# timer.net
KiCad netlist of a schematic drawn in Altium Designer
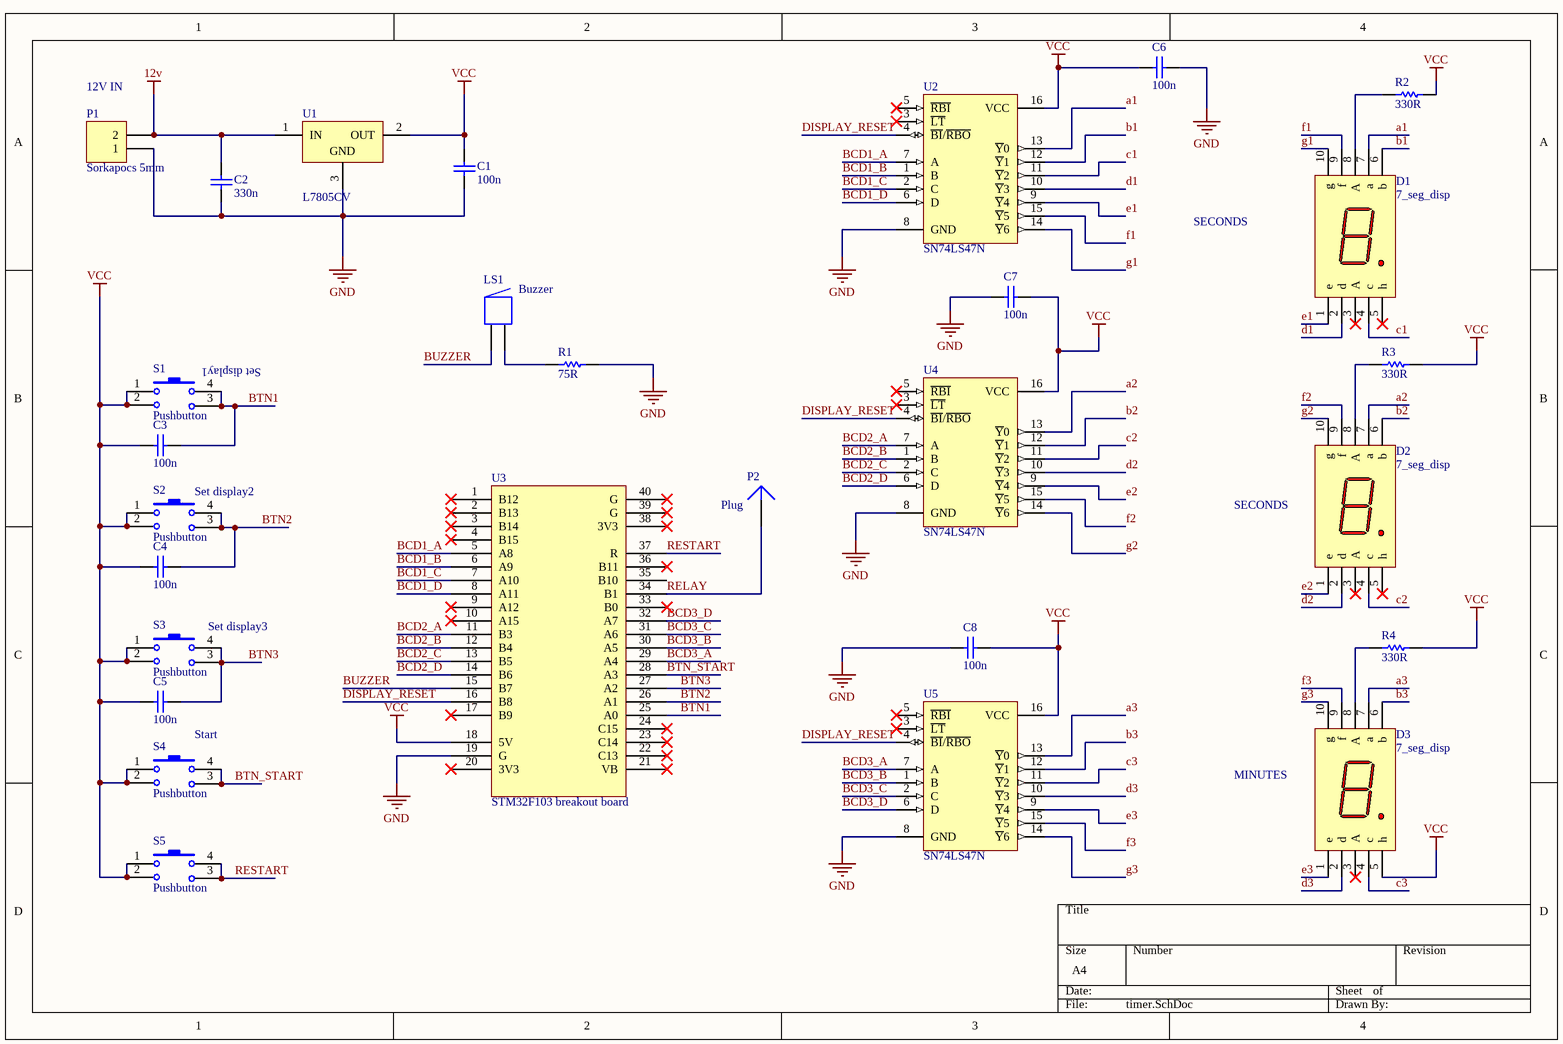
[diagram p0: timer.SchDoc]

(export (version "E")
  (design (tool "Eeschema 10.0.6"))
  (components
    (comp (ref "C1")
      (value "100n")
      (footprint "cap 100mil")
      (description "Capacitor")
      (fields (field (name "PUBLISHER") "Altium Limited"))
      (libsource (lib "Miscellaneous Devices") (part "Cap"))
    )
    (comp (ref "C2")
      (value "330n")
      (footprint "cap 5mm")
      (description "Capacitor")
      (fields (field (name "PUBLISHER") "Altium Limited"))
      (libsource (lib "Miscellaneous Devices") (part "Cap"))
    )
    (comp (ref "C3")
      (value "100n")
      (footprint "cap 100mil")
      (description "Capacitor")
      (fields (field (name "PUBLISHER") "Altium Limited"))
      (libsource (lib "Miscellaneous Devices") (part "Cap"))
    )
    (comp (ref "C4")
      (value "100n")
      (footprint "cap 100mil")
      (description "Capacitor")
      (fields (field (name "PUBLISHER") "Altium Limited"))
      (libsource (lib "Miscellaneous Devices") (part "Cap"))
    )
    (comp (ref "C5")
      (value "100n")
      (footprint "cap 100mil")
      (description "Capacitor")
      (fields (field (name "PUBLISHER") "Altium Limited"))
      (libsource (lib "Miscellaneous Devices") (part "Cap"))
    )
    (comp (ref "C6")
      (value "100n")
      (footprint "cap 100mil")
      (description "Capacitor")
      (fields (field (name "PUBLISHER") "Altium Limited"))
      (libsource (lib "Miscellaneous Devices") (part "Cap"))
    )
    (comp (ref "C7")
      (value "100n")
      (footprint "cap 100mil")
      (description "Capacitor")
      (fields (field (name "PUBLISHER") "Altium Limited"))
      (libsource (lib "Miscellaneous Devices") (part "Cap"))
    )
    (comp (ref "C8")
      (value "100n")
      (footprint "cap 100mil")
      (description "Capacitor")
      (fields (field (name "PUBLISHER") "Altium Limited"))
      (libsource (lib "Miscellaneous Devices") (part "Cap"))
    )
    (comp (ref "D1")
      (value "7_seg_disp")
      (footprint "Seven segment display")
      (libsource (lib "mySchematics") (part "7_seg_disp"))
    )
    (comp (ref "D2")
      (value "7_seg_disp")
      (footprint "Seven segment display")
      (libsource (lib "mySchematics") (part "7_seg_disp"))
    )
    (comp (ref "D3")
      (value "7_seg_disp")
      (footprint "Seven segment display")
      (libsource (lib "mySchematics") (part "7_seg_disp"))
    )
    (comp (ref "LS1")
      (value "Buzzer")
      (footprint "Buzzer")
      (description "Magnetic Transducer Buzzer")
      (fields (field (name "PUBLISHER") "Altium Limited"))
      (libsource (lib "Miscellaneous Devices") (part "Buzzer"))
    )
    (comp (ref "P1")
      (value "Sorkapocs 5mm")
      (footprint "SORKAPOCS-2")
      (description "Header, 2-Pin")
      (fields (field (name "PUBLISHER") "Altium Limited"))
      (libsource (lib "Miscellaneous Connectors") (part "Header 2"))
    )
    (comp (ref "P2")
      (value "Plug")
      (footprint "pad")
      (fields (field (name "PUBLISHER") "Altium Limited"))
      (libsource (lib "Miscellaneous Connectors") (part "Plug"))
    )
    (comp (ref "R1")
      (value "75R")
      (footprint "AXIAL-0.4")
      (description "Resistor")
      (fields (field (name "PUBLISHER") "Altium Limited"))
      (libsource (lib "Miscellaneous Devices") (part "Res1"))
    )
    (comp (ref "R2")
      (value "330R")
      (footprint "AXIAL-0.4")
      (description "Resistor")
      (fields (field (name "PUBLISHER") "Altium Limited"))
      (libsource (lib "Miscellaneous Devices") (part "Res1"))
    )
    (comp (ref "R3")
      (value "330R")
      (footprint "AXIAL-0.4")
      (description "Resistor")
      (fields (field (name "PUBLISHER") "Altium Limited"))
      (libsource (lib "Miscellaneous Devices") (part "Res1"))
    )
    (comp (ref "R4")
      (value "330R")
      (footprint "AXIAL-0.4")
      (description "Resistor")
      (fields (field (name "PUBLISHER") "Altium Limited"))
      (libsource (lib "Miscellaneous Devices") (part "Res1"))
    )
    (comp (ref "S1")
      (value "Pushbutton")
      (footprint "Pushbutton")
      (description "FSM2JSMLS -  Tactile Switch, Illuminated, 24 V, 50 mA, 100 gf, SMD, FSMJSM Series")
      (libsource (lib "mySchematics") (part "Tactile switch"))
    )
    (comp (ref "S2")
      (value "Pushbutton")
      (footprint "Pushbutton")
      (description "FSM2JSMLS -  Tactile Switch, Illuminated, 24 V, 50 mA, 100 gf, SMD, FSMJSM Series")
      (libsource (lib "mySchematics") (part "Tactile switch"))
    )
    (comp (ref "S3")
      (value "Pushbutton")
      (footprint "Pushbutton")
      (description "FSM2JSMLS -  Tactile Switch, Illuminated, 24 V, 50 mA, 100 gf, SMD, FSMJSM Series")
      (libsource (lib "mySchematics") (part "Tactile switch"))
    )
    (comp (ref "S4")
      (value "Pushbutton")
      (footprint "Pushbutton")
      (description "FSM2JSMLS -  Tactile Switch, Illuminated, 24 V, 50 mA, 100 gf, SMD, FSMJSM Series")
      (libsource (lib "mySchematics") (part "Tactile switch"))
    )
    (comp (ref "S5")
      (value "Pushbutton")
      (footprint "Pushbutton")
      (description "FSM2JSMLS -  Tactile Switch, Illuminated, 24 V, 50 mA, 100 gf, SMD, FSMJSM Series")
      (libsource (lib "mySchematics") (part "Tactile switch"))
    )
    (comp (ref "U1")
      (value "L7805CV")
      (footprint "TO220ABN")
      (description "Positive Voltage Regulator")
      (fields (field (name "PUBLISHER") "Altium Limited"))
      (libsource (lib "ST Power Mgt Voltage Regulator") (part "L7805CV"))
    )
    (comp (ref "U2")
      (value "SN74LS47N")
      (footprint "648-08")
      (description "BCD to 7-Segment Decoder/Driver")
      (fields (field (name "PUBLISHER") "Altium Limited"))
      (libsource (lib "ON Semi Logic Decoder Demux") (part "SN74LS47N"))
    )
    (comp (ref "U3")
      (value "STM32F103 breakout board")
      (footprint "STM32 BLUE PILL")
      (libsource (lib "mySchematics") (part "STM32F103 breakout board"))
    )
    (comp (ref "U4")
      (value "SN74LS47N")
      (footprint "648-08")
      (description "BCD to 7-Segment Decoder/Driver")
      (fields (field (name "PUBLISHER") "Altium Limited"))
      (libsource (lib "ON Semi Logic Decoder Demux") (part "SN74LS47N"))
    )
    (comp (ref "U5")
      (value "SN74LS47N")
      (footprint "648-08")
      (description "BCD to 7-Segment Decoder/Driver")
      (fields (field (name "PUBLISHER") "Altium Limited"))
      (libsource (lib "ON Semi Logic Decoder Demux") (part "SN74LS47N"))
    )
  )
  (nets
    (net (code "1") (name "/BCD1_A") (class "Default")
      (node (ref "U2") (pin "7") (pinfunction "A_7") (pintype "input"))
      (node (ref "U3") (pin "5") (pinfunction "A8_5") (pintype "passive"))
    )
    (net (code "2") (name "/BCD1_B") (class "Default")
      (node (ref "U2") (pin "1") (pinfunction "B_1") (pintype "input"))
      (node (ref "U3") (pin "6") (pinfunction "A9_6") (pintype "passive"))
    )
    (net (code "3") (name "/BCD1_C") (class "Default")
      (node (ref "U2") (pin "2") (pinfunction "C_2") (pintype "input"))
      (node (ref "U3") (pin "7") (pinfunction "A10_7") (pintype "passive"))
    )
    (net (code "4") (name "/BCD1_D") (class "Default")
      (node (ref "U2") (pin "6") (pinfunction "D_6") (pintype "input"))
      (node (ref "U3") (pin "8") (pinfunction "A11_8") (pintype "passive"))
    )
    (net (code "5") (name "/BCD2_A") (class "Default")
      (node (ref "U3") (pin "11") (pinfunction "B3_11") (pintype "passive"))
      (node (ref "U4") (pin "7") (pinfunction "A_7") (pintype "input"))
    )
    (net (code "6") (name "/BCD2_B") (class "Default")
      (node (ref "U3") (pin "12") (pinfunction "B4_12") (pintype "passive"))
      (node (ref "U4") (pin "1") (pinfunction "B_1") (pintype "input"))
    )
    (net (code "7") (name "/BCD2_C") (class "Default")
      (node (ref "U3") (pin "13") (pinfunction "B5_13") (pintype "passive"))
      (node (ref "U4") (pin "2") (pinfunction "C_2") (pintype "input"))
    )
    (net (code "8") (name "/BCD2_D") (class "Default")
      (node (ref "U3") (pin "14") (pinfunction "B6_14") (pintype "passive"))
      (node (ref "U4") (pin "6") (pinfunction "D_6") (pintype "input"))
    )
    (net (code "9") (name "/BCD3_A") (class "Default")
      (node (ref "U3") (pin "29") (pinfunction "A4_29") (pintype "passive"))
      (node (ref "U5") (pin "7") (pinfunction "A_7") (pintype "input"))
    )
    (net (code "10") (name "/BCD3_B") (class "Default")
      (node (ref "U3") (pin "30") (pinfunction "A5_30") (pintype "passive"))
      (node (ref "U5") (pin "1") (pinfunction "B_1") (pintype "input"))
    )
    (net (code "11") (name "/BCD3_C") (class "Default")
      (node (ref "U3") (pin "31") (pinfunction "A6_31") (pintype "passive"))
      (node (ref "U5") (pin "2") (pinfunction "C_2") (pintype "input"))
    )
    (net (code "12") (name "/BCD3_D") (class "Default")
      (node (ref "U3") (pin "32") (pinfunction "A7_32") (pintype "passive"))
      (node (ref "U5") (pin "6") (pinfunction "D_6") (pintype "input"))
    )
    (net (code "13") (name "/BTN1") (class "Default")
      (node (ref "C3") (pin "1") (pinfunction "1_1") (pintype "passive"))
      (node (ref "S1") (pin "3") (pinfunction "3_3") (pintype "passive"))
      (node (ref "S1") (pin "4") (pinfunction "4_4") (pintype "passive"))
      (node (ref "U3") (pin "25") (pinfunction "A0_25") (pintype "passive"))
    )
    (net (code "14") (name "/BTN2") (class "Default")
      (node (ref "C4") (pin "1") (pinfunction "1_1") (pintype "passive"))
      (node (ref "S2") (pin "3") (pinfunction "3_3") (pintype "passive"))
      (node (ref "S2") (pin "4") (pinfunction "4_4") (pintype "passive"))
      (node (ref "U3") (pin "26") (pinfunction "A1_26") (pintype "passive"))
    )
    (net (code "15") (name "/BTN3") (class "Default")
      (node (ref "C5") (pin "1") (pinfunction "1_1") (pintype "passive"))
      (node (ref "S3") (pin "3") (pinfunction "3_3") (pintype "passive"))
      (node (ref "S3") (pin "4") (pinfunction "4_4") (pintype "passive"))
      (node (ref "U3") (pin "27") (pinfunction "A2_27") (pintype "passive"))
    )
    (net (code "16") (name "/BTN_START") (class "Default")
      (node (ref "S4") (pin "3") (pinfunction "3_3") (pintype "passive"))
      (node (ref "S4") (pin "4") (pinfunction "4_4") (pintype "passive"))
      (node (ref "U3") (pin "28") (pinfunction "A3_28") (pintype "passive"))
    )
    (net (code "17") (name "/BUZZER") (class "Default")
      (node (ref "LS1") (pin "1") (pinfunction "1_1") (pintype "passive"))
      (node (ref "U3") (pin "15") (pinfunction "B7_15") (pintype "passive"))
    )
    (net (code "18") (name "/DISPLAY_RESET") (class "Default")
      (node (ref "U2") (pin "4") (pinfunction "~{BI}/~{RBO}_4") (pintype "bidirectional"))
      (node (ref "U3") (pin "16") (pinfunction "B8_16") (pintype "passive"))
      (node (ref "U4") (pin "4") (pinfunction "~{BI}/~{RBO}_4") (pintype "bidirectional"))
      (node (ref "U5") (pin "4") (pinfunction "~{BI}/~{RBO}_4") (pintype "bidirectional"))
    )
    (net (code "19") (name "/RELAY") (class "Default")
      (node (ref "P2") (pin "1") (pinfunction "1_1") (pintype "passive"))
      (node (ref "U3") (pin "34") (pinfunction "B1_34") (pintype "passive"))
    )
    (net (code "20") (name "/RESTART") (class "Default")
      (node (ref "S5") (pin "3") (pinfunction "3_3") (pintype "passive"))
      (node (ref "S5") (pin "4") (pinfunction "4_4") (pintype "passive"))
      (node (ref "U3") (pin "37") (pinfunction "R_37") (pintype "passive"))
    )
    (net (code "21") (name "/a1") (class "Default")
      (node (ref "D1") (pin "7") (pinfunction "a_7") (pintype "passive"))
      (node (ref "U2") (pin "13") (pinfunction "~{Y}0_13") (pintype "output"))
    )
    (net (code "22") (name "/a2") (class "Default")
      (node (ref "D2") (pin "7") (pinfunction "a_7") (pintype "passive"))
      (node (ref "U4") (pin "13") (pinfunction "~{Y}0_13") (pintype "output"))
    )
    (net (code "23") (name "/a3") (class "Default")
      (node (ref "D3") (pin "7") (pinfunction "a_7") (pintype "passive"))
      (node (ref "U5") (pin "13") (pinfunction "~{Y}0_13") (pintype "output"))
    )
    (net (code "24") (name "/b1") (class "Default")
      (node (ref "D1") (pin "6") (pinfunction "b_6") (pintype "passive"))
      (node (ref "U2") (pin "12") (pinfunction "~{Y}1_12") (pintype "output"))
    )
    (net (code "25") (name "/b2") (class "Default")
      (node (ref "D2") (pin "6") (pinfunction "b_6") (pintype "passive"))
      (node (ref "U4") (pin "12") (pinfunction "~{Y}1_12") (pintype "output"))
    )
    (net (code "26") (name "/b3") (class "Default")
      (node (ref "D3") (pin "6") (pinfunction "b_6") (pintype "passive"))
      (node (ref "U5") (pin "12") (pinfunction "~{Y}1_12") (pintype "output"))
    )
    (net (code "27") (name "/c1") (class "Default")
      (node (ref "D1") (pin "4") (pinfunction "c_4") (pintype "passive"))
      (node (ref "U2") (pin "11") (pinfunction "~{Y}2_11") (pintype "output"))
    )
    (net (code "28") (name "/c2") (class "Default")
      (node (ref "D2") (pin "4") (pinfunction "c_4") (pintype "passive"))
      (node (ref "U4") (pin "11") (pinfunction "~{Y}2_11") (pintype "output"))
    )
    (net (code "29") (name "/c3") (class "Default")
      (node (ref "D3") (pin "4") (pinfunction "c_4") (pintype "passive"))
      (node (ref "U5") (pin "11") (pinfunction "~{Y}2_11") (pintype "output"))
    )
    (net (code "30") (name "/d1") (class "Default")
      (node (ref "D1") (pin "2") (pinfunction "d_2") (pintype "passive"))
      (node (ref "U2") (pin "10") (pinfunction "~{Y}3_10") (pintype "output"))
    )
    (net (code "31") (name "/d2") (class "Default")
      (node (ref "D2") (pin "2") (pinfunction "d_2") (pintype "passive"))
      (node (ref "U4") (pin "10") (pinfunction "~{Y}3_10") (pintype "output"))
    )
    (net (code "32") (name "/d3") (class "Default")
      (node (ref "D3") (pin "2") (pinfunction "d_2") (pintype "passive"))
      (node (ref "U5") (pin "10") (pinfunction "~{Y}3_10") (pintype "output"))
    )
    (net (code "33") (name "/e1") (class "Default")
      (node (ref "D1") (pin "1") (pinfunction "e_1") (pintype "passive"))
      (node (ref "U2") (pin "9") (pinfunction "~{Y}4_9") (pintype "output"))
    )
    (net (code "34") (name "/e2") (class "Default")
      (node (ref "D2") (pin "1") (pinfunction "e_1") (pintype "passive"))
      (node (ref "U4") (pin "9") (pinfunction "~{Y}4_9") (pintype "output"))
    )
    (net (code "35") (name "/e3") (class "Default")
      (node (ref "D3") (pin "1") (pinfunction "e_1") (pintype "passive"))
      (node (ref "U5") (pin "9") (pinfunction "~{Y}4_9") (pintype "output"))
    )
    (net (code "36") (name "/f1") (class "Default")
      (node (ref "D1") (pin "9") (pinfunction "f_9") (pintype "passive"))
      (node (ref "U2") (pin "15") (pinfunction "~{Y}5_15") (pintype "output"))
    )
    (net (code "37") (name "/f2") (class "Default")
      (node (ref "D2") (pin "9") (pinfunction "f_9") (pintype "passive"))
      (node (ref "U4") (pin "15") (pinfunction "~{Y}5_15") (pintype "output"))
    )
    (net (code "38") (name "/f3") (class "Default")
      (node (ref "D3") (pin "9") (pinfunction "f_9") (pintype "passive"))
      (node (ref "U5") (pin "15") (pinfunction "~{Y}5_15") (pintype "output"))
    )
    (net (code "39") (name "/g1") (class "Default")
      (node (ref "D1") (pin "10") (pinfunction "g_10") (pintype "passive"))
      (node (ref "U2") (pin "14") (pinfunction "~{Y}6_14") (pintype "output"))
    )
    (net (code "40") (name "/g2") (class "Default")
      (node (ref "D2") (pin "10") (pinfunction "g_10") (pintype "passive"))
      (node (ref "U4") (pin "14") (pinfunction "~{Y}6_14") (pintype "output"))
    )
    (net (code "41") (name "/g3") (class "Default")
      (node (ref "D3") (pin "10") (pinfunction "g_10") (pintype "passive"))
      (node (ref "U5") (pin "14") (pinfunction "~{Y}6_14") (pintype "output"))
    )
    (net (code "42") (name "12v") (class "Default")
      (node (ref "C2") (pin "2") (pinfunction "2_2") (pintype "passive"))
      (node (ref "P1") (pin "2") (pinfunction "2_2") (pintype "passive"))
      (node (ref "U1") (pin "1") (pinfunction "IN_1") (pintype "power_in"))
    )
    (net (code "43") (name "GND") (class "Default")
      (node (ref "C1") (pin "1") (pinfunction "1_1") (pintype "passive"))
      (node (ref "C2") (pin "1") (pinfunction "1_1") (pintype "passive"))
      (node (ref "C6") (pin "1") (pinfunction "1_1") (pintype "passive"))
      (node (ref "C7") (pin "2") (pinfunction "2_2") (pintype "passive"))
      (node (ref "C8") (pin "2") (pinfunction "2_2") (pintype "passive"))
      (node (ref "P1") (pin "1") (pinfunction "1_1") (pintype "passive"))
      (node (ref "R1") (pin "2") (pinfunction "2_2") (pintype "passive"))
      (node (ref "U1") (pin "3") (pinfunction "GND_3") (pintype "power_in"))
      (node (ref "U2") (pin "8") (pinfunction "GND_8") (pintype "power_in"))
      (node (ref "U3") (pin "19") (pinfunction "G_19") (pintype "passive"))
      (node (ref "U4") (pin "8") (pinfunction "GND_8") (pintype "power_in"))
      (node (ref "U5") (pin "8") (pinfunction "GND_8") (pintype "power_in"))
    )
    (net (code "44") (name "Net-(D1-A-Pad8)") (class "Default")
      (node (ref "D1") (pin "8") (pinfunction "A_8") (pintype "passive"))
      (node (ref "R2") (pin "1") (pinfunction "1_1") (pintype "passive"))
    )
    (net (code "45") (name "Net-(D2-A-Pad8)") (class "Default")
      (node (ref "D2") (pin "8") (pinfunction "A_8") (pintype "passive"))
      (node (ref "R3") (pin "1") (pinfunction "1_1") (pintype "passive"))
    )
    (net (code "46") (name "Net-(D3-A-Pad8)") (class "Default")
      (node (ref "D3") (pin "8") (pinfunction "A_8") (pintype "passive"))
      (node (ref "R4") (pin "1") (pinfunction "1_1") (pintype "passive"))
    )
    (net (code "47") (name "Net-(LS1-Pad2)") (class "Default")
      (node (ref "LS1") (pin "2") (pinfunction "2_2") (pintype "passive"))
      (node (ref "R1") (pin "1") (pinfunction "1_1") (pintype "passive"))
    )
    (net (code "48") (name "VCC") (class "Default")
      (node (ref "C1") (pin "2") (pinfunction "2_2") (pintype "passive"))
      (node (ref "C3") (pin "2") (pinfunction "2_2") (pintype "passive"))
      (node (ref "C4") (pin "2") (pinfunction "2_2") (pintype "passive"))
      (node (ref "C5") (pin "2") (pinfunction "2_2") (pintype "passive"))
      (node (ref "C6") (pin "2") (pinfunction "2_2") (pintype "passive"))
      (node (ref "C7") (pin "1") (pinfunction "1_1") (pintype "passive"))
      (node (ref "C8") (pin "1") (pinfunction "1_1") (pintype "passive"))
      (node (ref "D3") (pin "5") (pinfunction "h_5") (pintype "passive"))
      (node (ref "R2") (pin "2") (pinfunction "2_2") (pintype "passive"))
      (node (ref "R3") (pin "2") (pinfunction "2_2") (pintype "passive"))
      (node (ref "R4") (pin "2") (pinfunction "2_2") (pintype "passive"))
      (node (ref "S1") (pin "1") (pinfunction "1_1") (pintype "passive"))
      (node (ref "S1") (pin "2") (pinfunction "2_2") (pintype "passive"))
      (node (ref "S2") (pin "1") (pinfunction "1_1") (pintype "passive"))
      (node (ref "S2") (pin "2") (pinfunction "2_2") (pintype "passive"))
      (node (ref "S3") (pin "1") (pinfunction "1_1") (pintype "passive"))
      (node (ref "S3") (pin "2") (pinfunction "2_2") (pintype "passive"))
      (node (ref "S4") (pin "1") (pinfunction "1_1") (pintype "passive"))
      (node (ref "S4") (pin "2") (pinfunction "2_2") (pintype "passive"))
      (node (ref "S5") (pin "1") (pinfunction "1_1") (pintype "passive"))
      (node (ref "S5") (pin "2") (pinfunction "2_2") (pintype "passive"))
      (node (ref "U1") (pin "2") (pinfunction "OUT_2") (pintype "power_in"))
      (node (ref "U2") (pin "16") (pinfunction "VCC_16") (pintype "power_in"))
      (node (ref "U3") (pin "18") (pinfunction "5V_18") (pintype "passive"))
      (node (ref "U4") (pin "16") (pinfunction "VCC_16") (pintype "power_in"))
      (node (ref "U5") (pin "16") (pinfunction "VCC_16") (pintype "power_in"))
    )
    (net (code "49") (name "unconnected-(D1-A-Pad3)") (class "Default")
      (node (ref "D1") (pin "3") (pinfunction "A_3") (pintype "passive+no_connect"))
    )
    (net (code "50") (name "unconnected-(D1-h-Pad5)") (class "Default")
      (node (ref "D1") (pin "5") (pinfunction "h_5") (pintype "passive+no_connect"))
    )
    (net (code "51") (name "unconnected-(D2-A-Pad3)") (class "Default")
      (node (ref "D2") (pin "3") (pinfunction "A_3") (pintype "passive+no_connect"))
    )
    (net (code "52") (name "unconnected-(D2-h-Pad5)") (class "Default")
      (node (ref "D2") (pin "5") (pinfunction "h_5") (pintype "passive+no_connect"))
    )
    (net (code "53") (name "unconnected-(D3-A-Pad3)") (class "Default")
      (node (ref "D3") (pin "3") (pinfunction "A_3") (pintype "passive+no_connect"))
    )
    (net (code "54") (name "unconnected-(U2-~{LT}-Pad3)") (class "Default")
      (node (ref "U2") (pin "3") (pinfunction "~{LT}_3") (pintype "input+no_connect"))
    )
    (net (code "55") (name "unconnected-(U2-~{RBI}-Pad5)") (class "Default")
      (node (ref "U2") (pin "5") (pinfunction "~{RBI}_5") (pintype "input+no_connect"))
    )
    (net (code "56") (name "unconnected-(U3-3V3-Pad20)") (class "Default")
      (node (ref "U3") (pin "20") (pinfunction "3V3_20") (pintype "passive+no_connect"))
    )
    (net (code "57") (name "unconnected-(U3-3V3-Pad38)") (class "Default")
      (node (ref "U3") (pin "38") (pinfunction "3V3_38") (pintype "passive+no_connect"))
    )
    (net (code "58") (name "unconnected-(U3-A12-Pad9)") (class "Default")
      (node (ref "U3") (pin "9") (pinfunction "A12_9") (pintype "passive+no_connect"))
    )
    (net (code "59") (name "unconnected-(U3-A15-Pad10)") (class "Default")
      (node (ref "U3") (pin "10") (pinfunction "A15_10") (pintype "passive+no_connect"))
    )
    (net (code "60") (name "unconnected-(U3-B0-Pad33)") (class "Default")
      (node (ref "U3") (pin "33") (pinfunction "B0_33") (pintype "passive+no_connect"))
    )
    (net (code "61") (name "unconnected-(U3-B9-Pad17)") (class "Default")
      (node (ref "U3") (pin "17") (pinfunction "B9_17") (pintype "passive+no_connect"))
    )
    (net (code "62") (name "unconnected-(U3-B10-Pad35)") (class "Default")
      (node (ref "U3") (pin "35") (pinfunction "B10_35") (pintype "passive"))
    )
    (net (code "63") (name "unconnected-(U3-B11-Pad36)") (class "Default")
      (node (ref "U3") (pin "36") (pinfunction "B11_36") (pintype "passive+no_connect"))
    )
    (net (code "64") (name "unconnected-(U3-B12-Pad1)") (class "Default")
      (node (ref "U3") (pin "1") (pinfunction "B12_1") (pintype "passive+no_connect"))
    )
    (net (code "65") (name "unconnected-(U3-B13-Pad2)") (class "Default")
      (node (ref "U3") (pin "2") (pinfunction "B13_2") (pintype "passive+no_connect"))
    )
    (net (code "66") (name "unconnected-(U3-B14-Pad3)") (class "Default")
      (node (ref "U3") (pin "3") (pinfunction "B14_3") (pintype "passive+no_connect"))
    )
    (net (code "67") (name "unconnected-(U3-B15-Pad4)") (class "Default")
      (node (ref "U3") (pin "4") (pinfunction "B15_4") (pintype "passive+no_connect"))
    )
    (net (code "68") (name "unconnected-(U3-C13-Pad22)") (class "Default")
      (node (ref "U3") (pin "22") (pinfunction "C13_22") (pintype "passive+no_connect"))
    )
    (net (code "69") (name "unconnected-(U3-C14-Pad23)") (class "Default")
      (node (ref "U3") (pin "23") (pinfunction "C14_23") (pintype "passive+no_connect"))
    )
    (net (code "70") (name "unconnected-(U3-C15-Pad24)") (class "Default")
      (node (ref "U3") (pin "24") (pinfunction "C15_24") (pintype "passive+no_connect"))
    )
    (net (code "71") (name "unconnected-(U3-G-Pad39)") (class "Default")
      (node (ref "U3") (pin "39") (pinfunction "G_39") (pintype "passive+no_connect"))
    )
    (net (code "72") (name "unconnected-(U3-G-Pad40)") (class "Default")
      (node (ref "U3") (pin "40") (pinfunction "G_40") (pintype "passive+no_connect"))
    )
    (net (code "73") (name "unconnected-(U3-VB-Pad21)") (class "Default")
      (node (ref "U3") (pin "21") (pinfunction "VB_21") (pintype "passive+no_connect"))
    )
    (net (code "74") (name "unconnected-(U4-~{LT}-Pad3)") (class "Default")
      (node (ref "U4") (pin "3") (pinfunction "~{LT}_3") (pintype "input+no_connect"))
    )
    (net (code "75") (name "unconnected-(U4-~{RBI}-Pad5)") (class "Default")
      (node (ref "U4") (pin "5") (pinfunction "~{RBI}_5") (pintype "input+no_connect"))
    )
    (net (code "76") (name "unconnected-(U5-~{LT}-Pad3)") (class "Default")
      (node (ref "U5") (pin "3") (pinfunction "~{LT}_3") (pintype "input+no_connect"))
    )
    (net (code "77") (name "unconnected-(U5-~{RBI}-Pad5)") (class "Default")
      (node (ref "U5") (pin "5") (pinfunction "~{RBI}_5") (pintype "input+no_connect"))
    )
  )
)
